# untitled.net
KiCad netlist of a schematic drawn in EAGLE
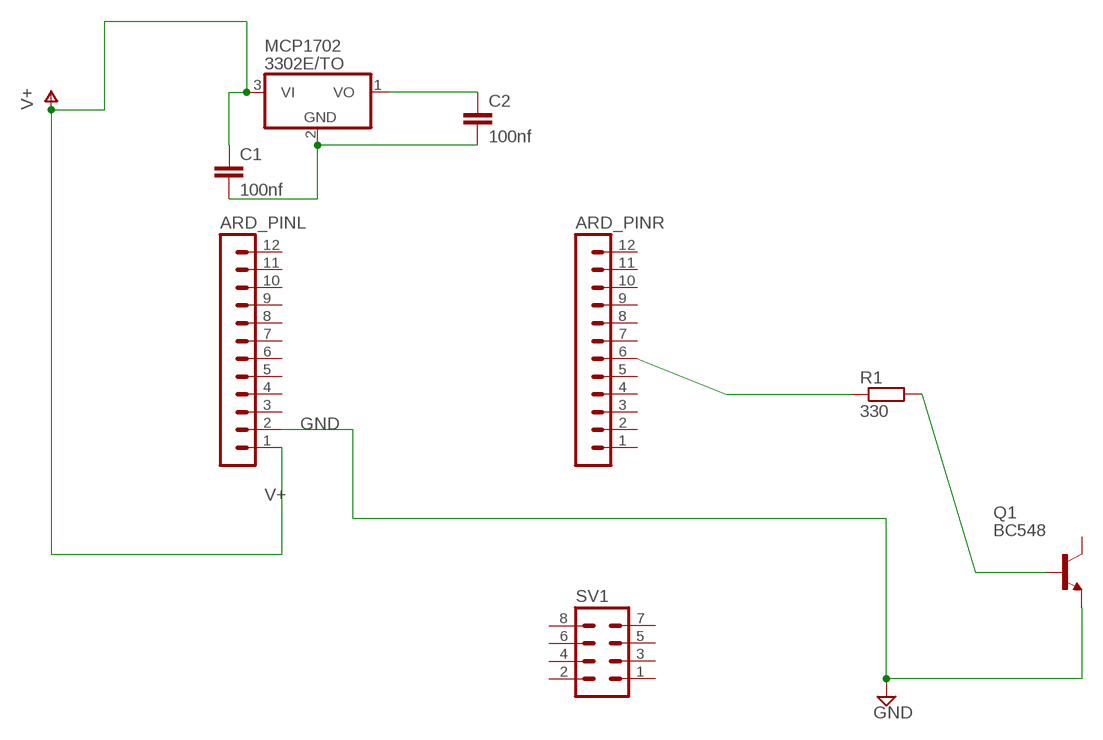
[diagram p0: schematic, sheet 1]

(export (version "E")
  (design (tool "Eeschema 10.0.6"))
  (components
    (comp (ref "ARD_PINL")
      (value "MA12-1")
      (footprint "eagle-import:MA12-1")
      (libsource (lib "eagle-import") (part "MA12-1"))
    )
    (comp (ref "ARD_PINR")
      (value "MA12-1")
      (footprint "eagle-import:MA12-1")
      (libsource (lib "eagle-import") (part "MA12-1"))
    )
    (comp (ref "C1")
      (value "100nf")
      (footprint "eagle-import:C025-024X044")
      (libsource (lib "eagle-import") (part "C-EU025-024X044"))
    )
    (comp (ref "C2")
      (value "100nf")
      (footprint "eagle-import:C025-024X044")
      (libsource (lib "eagle-import") (part "C-EU025-024X044"))
    )
    (comp (ref "MCP1702")
      (value "3302E/TO")
      (footprint "eagle-import:TO92")
      (libsource (lib "eagle-import") (part "78ZL05"))
    )
    (comp (ref "Q1")
      (value "BC548")
      (footprint "eagle-import:TO92-EBC")
      (libsource (lib "eagle-import") (part "BC548"))
    )
    (comp (ref "R1")
      (value "330")
      (footprint "eagle-import:0204V")
      (libsource (lib "eagle-import") (part "R-EU_0204/2V"))
    )
    (comp (ref "SV1")
      (value "MA04-2")
      (footprint "eagle-import:MA04-2")
      (libsource (lib "eagle-import") (part "MA04-2"))
    )
  )
  (nets
    (net (code "1") (name "GND") (class "Default")
      (node (ref "ARD_PINL") (pin "2") (pinfunction "2_2") (pintype "passive"))
      (node (ref "Q1") (pin "E") (pinfunction "E_E") (pintype "passive"))
    )
    (net (code "2") (name "Net-(ARD_PINR-Pad6)") (class "Default")
      (node (ref "ARD_PINR") (pin "6") (pinfunction "6_6") (pintype "passive"))
      (node (ref "R1") (pin "1") (pinfunction "1_1") (pintype "passive"))
    )
    (net (code "3") (name "Net-(MCP1702-GND)") (class "Default")
      (node (ref "C1") (pin "2") (pinfunction "2_2") (pintype "passive"))
      (node (ref "C2") (pin "2") (pinfunction "2_2") (pintype "passive"))
      (node (ref "MCP1702") (pin "2") (pinfunction "GND_2") (pintype "passive"))
    )
    (net (code "4") (name "Net-(MCP1702-VO)") (class "Default")
      (node (ref "C2") (pin "1") (pinfunction "1_1") (pintype "passive"))
      (node (ref "MCP1702") (pin "1") (pinfunction "VO_1") (pintype "passive"))
    )
    (net (code "5") (name "Net-(Q1-PadB)") (class "Default")
      (node (ref "Q1") (pin "B") (pinfunction "B_B") (pintype "passive"))
      (node (ref "R1") (pin "2") (pinfunction "2_2") (pintype "passive"))
    )
    (net (code "6") (name "V+") (class "Default")
      (node (ref "ARD_PINL") (pin "1") (pinfunction "1_1") (pintype "passive"))
      (node (ref "C1") (pin "1") (pinfunction "1_1") (pintype "passive"))
      (node (ref "MCP1702") (pin "3") (pinfunction "VI_3") (pintype "input"))
    )
    (net (code "7") (name "unconnected-(ARD_PINL-Pad3)") (class "Default")
      (node (ref "ARD_PINL") (pin "3") (pinfunction "3_3") (pintype "passive"))
    )
    (net (code "8") (name "unconnected-(ARD_PINL-Pad4)") (class "Default")
      (node (ref "ARD_PINL") (pin "4") (pinfunction "4_4") (pintype "passive"))
    )
    (net (code "9") (name "unconnected-(ARD_PINL-Pad5)") (class "Default")
      (node (ref "ARD_PINL") (pin "5") (pinfunction "5_5") (pintype "passive"))
    )
    (net (code "10") (name "unconnected-(ARD_PINL-Pad6)") (class "Default")
      (node (ref "ARD_PINL") (pin "6") (pinfunction "6_6") (pintype "passive"))
    )
    (net (code "11") (name "unconnected-(ARD_PINL-Pad7)") (class "Default")
      (node (ref "ARD_PINL") (pin "7") (pinfunction "7_7") (pintype "passive"))
    )
    (net (code "12") (name "unconnected-(ARD_PINL-Pad8)") (class "Default")
      (node (ref "ARD_PINL") (pin "8") (pinfunction "8_8") (pintype "passive"))
    )
    (net (code "13") (name "unconnected-(ARD_PINL-Pad9)") (class "Default")
      (node (ref "ARD_PINL") (pin "9") (pinfunction "9_9") (pintype "passive"))
    )
    (net (code "14") (name "unconnected-(ARD_PINL-Pad10)") (class "Default")
      (node (ref "ARD_PINL") (pin "10") (pinfunction "10_10") (pintype "passive"))
    )
    (net (code "15") (name "unconnected-(ARD_PINL-Pad11)") (class "Default")
      (node (ref "ARD_PINL") (pin "11") (pinfunction "11_11") (pintype "passive"))
    )
    (net (code "16") (name "unconnected-(ARD_PINL-Pad12)") (class "Default")
      (node (ref "ARD_PINL") (pin "12") (pinfunction "12_12") (pintype "passive"))
    )
    (net (code "17") (name "unconnected-(ARD_PINR-Pad1)") (class "Default")
      (node (ref "ARD_PINR") (pin "1") (pinfunction "1_1") (pintype "passive"))
    )
    (net (code "18") (name "unconnected-(ARD_PINR-Pad2)") (class "Default")
      (node (ref "ARD_PINR") (pin "2") (pinfunction "2_2") (pintype "passive"))
    )
    (net (code "19") (name "unconnected-(ARD_PINR-Pad3)") (class "Default")
      (node (ref "ARD_PINR") (pin "3") (pinfunction "3_3") (pintype "passive"))
    )
    (net (code "20") (name "unconnected-(ARD_PINR-Pad4)") (class "Default")
      (node (ref "ARD_PINR") (pin "4") (pinfunction "4_4") (pintype "passive"))
    )
    (net (code "21") (name "unconnected-(ARD_PINR-Pad5)") (class "Default")
      (node (ref "ARD_PINR") (pin "5") (pinfunction "5_5") (pintype "passive"))
    )
    (net (code "22") (name "unconnected-(ARD_PINR-Pad7)") (class "Default")
      (node (ref "ARD_PINR") (pin "7") (pinfunction "7_7") (pintype "passive"))
    )
    (net (code "23") (name "unconnected-(ARD_PINR-Pad8)") (class "Default")
      (node (ref "ARD_PINR") (pin "8") (pinfunction "8_8") (pintype "passive"))
    )
    (net (code "24") (name "unconnected-(ARD_PINR-Pad9)") (class "Default")
      (node (ref "ARD_PINR") (pin "9") (pinfunction "9_9") (pintype "passive"))
    )
    (net (code "25") (name "unconnected-(ARD_PINR-Pad10)") (class "Default")
      (node (ref "ARD_PINR") (pin "10") (pinfunction "10_10") (pintype "passive"))
    )
    (net (code "26") (name "unconnected-(ARD_PINR-Pad11)") (class "Default")
      (node (ref "ARD_PINR") (pin "11") (pinfunction "11_11") (pintype "passive"))
    )
    (net (code "27") (name "unconnected-(ARD_PINR-Pad12)") (class "Default")
      (node (ref "ARD_PINR") (pin "12") (pinfunction "12_12") (pintype "passive"))
    )
    (net (code "28") (name "unconnected-(Q1-PadC)") (class "Default")
      (node (ref "Q1") (pin "C") (pinfunction "C_C") (pintype "passive"))
    )
    (net (code "29") (name "unconnected-(SV1-Pad1)") (class "Default")
      (node (ref "SV1") (pin "1") (pinfunction "1_1") (pintype "passive"))
    )
    (net (code "30") (name "unconnected-(SV1-Pad2)") (class "Default")
      (node (ref "SV1") (pin "2") (pinfunction "2_2") (pintype "passive"))
    )
    (net (code "31") (name "unconnected-(SV1-Pad3)") (class "Default")
      (node (ref "SV1") (pin "3") (pinfunction "3_3") (pintype "passive"))
    )
    (net (code "32") (name "unconnected-(SV1-Pad4)") (class "Default")
      (node (ref "SV1") (pin "4") (pinfunction "4_4") (pintype "passive"))
    )
    (net (code "33") (name "unconnected-(SV1-Pad5)") (class "Default")
      (node (ref "SV1") (pin "5") (pinfunction "5_5") (pintype "passive"))
    )
    (net (code "34") (name "unconnected-(SV1-Pad6)") (class "Default")
      (node (ref "SV1") (pin "6") (pinfunction "6_6") (pintype "passive"))
    )
    (net (code "35") (name "unconnected-(SV1-Pad7)") (class "Default")
      (node (ref "SV1") (pin "7") (pinfunction "7_7") (pintype "passive"))
    )
    (net (code "36") (name "unconnected-(SV1-Pad8)") (class "Default")
      (node (ref "SV1") (pin "8") (pinfunction "8_8") (pintype "passive"))
    )
  )
)
